# D1MiniRFM95.net
KiCad netlist of a schematic drawn in EAGLE
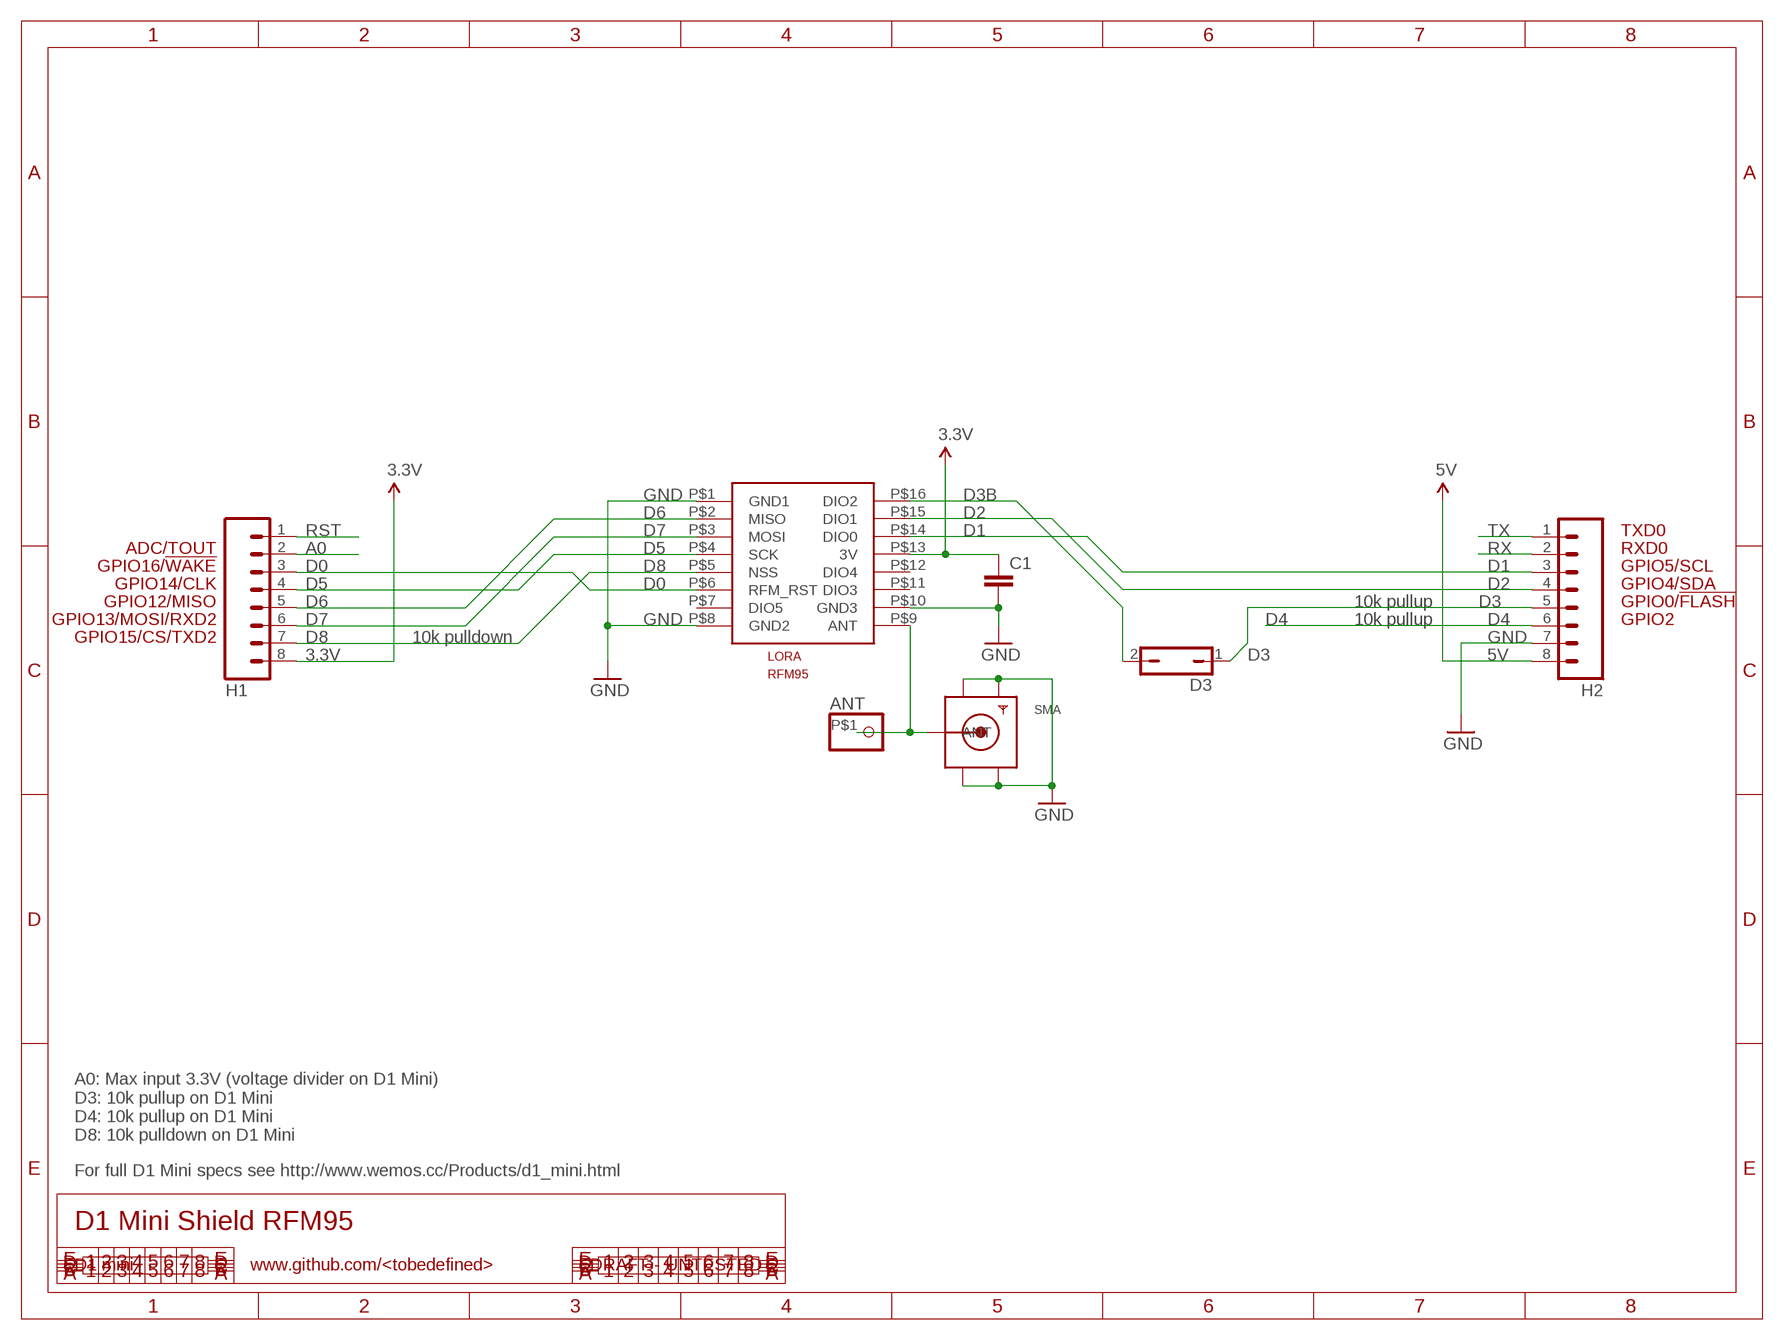
[diagram p0: schematic, sheet 1]

(export (version "E")
  (design (tool "Eeschema 10.0.6"))
  (components
    (comp (ref "ANT")
      (value "PINHD-1X1-BIGPOGO")
      (footprint "eagle-import:1X1-BIGPOGO")
      (libsource (lib "eagle-import") (part "PINHD-1X1-BIGPOGO"))
    )
    (comp (ref "C1")
      (value "C-EU025-024X044")
      (footprint "eagle-import:C025-024X044")
      (libsource (lib "eagle-import") (part "C-EU025-024X044"))
    )
    (comp (ref "D3")
      (value "JP1Q")
      (footprint "eagle-import:JP1")
      (libsource (lib "eagle-import") (part "JP1Q"))
    )
    (comp (ref "H1")
      (value "M08")
      (footprint "eagle-import:1X08")
      (libsource (lib "eagle-import") (part "M08"))
    )
    (comp (ref "H2")
      (value "M08")
      (footprint "eagle-import:1X08")
      (libsource (lib "eagle-import") (part "M08"))
    )
    (comp (ref "LORA")
      (value "RFM95")
      (footprint "eagle-import:RFM95")
      (libsource (lib "eagle-import") (part "RFM95"))
    )
    (comp (ref "SMA")
      (value "SMACONNECTOR_EDGE")
      (footprint "eagle-import:SMA_EDGELAUNCH")
      (libsource (lib "eagle-import") (part "SMACONNECTOR_EDGE"))
    )
  )
  (nets
    (net (code "1") (name "/A0") (class "Default")
      (node (ref "H1") (pin "2") (pinfunction "2_2") (pintype "passive"))
    )
    (net (code "2") (name "/D0") (class "Default")
      (node (ref "H1") (pin "3") (pinfunction "3_3") (pintype "passive"))
      (node (ref "LORA") (pin "P$6") (pinfunction "RFM_RST_P$6") (pintype "bidirectional"))
    )
    (net (code "3") (name "/D1") (class "Default")
      (node (ref "H2") (pin "3") (pinfunction "3_3") (pintype "passive"))
      (node (ref "LORA") (pin "P$14") (pinfunction "DIO0_P$14") (pintype "bidirectional"))
    )
    (net (code "4") (name "/D2") (class "Default")
      (node (ref "H2") (pin "4") (pinfunction "4_4") (pintype "passive"))
      (node (ref "LORA") (pin "P$15") (pinfunction "DIO1_P$15") (pintype "bidirectional"))
    )
    (net (code "5") (name "/D3") (class "Default")
      (node (ref "D3") (pin "1") (pinfunction "1_1") (pintype "passive"))
      (node (ref "H2") (pin "5") (pinfunction "5_5") (pintype "passive"))
    )
    (net (code "6") (name "/D3B") (class "Default")
      (node (ref "D3") (pin "2") (pinfunction "2_2") (pintype "passive"))
      (node (ref "LORA") (pin "P$16") (pinfunction "DIO2_P$16") (pintype "bidirectional"))
    )
    (net (code "7") (name "/D4") (class "Default")
      (node (ref "H2") (pin "6") (pinfunction "6_6") (pintype "passive"))
    )
    (net (code "8") (name "/D5") (class "Default")
      (node (ref "H1") (pin "4") (pinfunction "4_4") (pintype "passive"))
      (node (ref "LORA") (pin "P$4") (pinfunction "SCK_P$4") (pintype "bidirectional"))
    )
    (net (code "9") (name "/D6") (class "Default")
      (node (ref "H1") (pin "5") (pinfunction "5_5") (pintype "passive"))
      (node (ref "LORA") (pin "P$2") (pinfunction "MISO_P$2") (pintype "bidirectional"))
    )
    (net (code "10") (name "/D7") (class "Default")
      (node (ref "H1") (pin "6") (pinfunction "6_6") (pintype "passive"))
      (node (ref "LORA") (pin "P$3") (pinfunction "MOSI_P$3") (pintype "bidirectional"))
    )
    (net (code "11") (name "/D8") (class "Default")
      (node (ref "H1") (pin "7") (pinfunction "7_7") (pintype "passive"))
      (node (ref "LORA") (pin "P$5") (pinfunction "NSS_P$5") (pintype "bidirectional"))
    )
    (net (code "12") (name "/RST") (class "Default")
      (node (ref "H1") (pin "1") (pinfunction "1_1") (pintype "passive"))
    )
    (net (code "13") (name "/RX") (class "Default")
      (node (ref "H2") (pin "2") (pinfunction "2_2") (pintype "passive"))
    )
    (net (code "14") (name "/TX") (class "Default")
      (node (ref "H2") (pin "1") (pinfunction "1_1") (pintype "passive"))
    )
    (net (code "15") (name "3.3V") (class "Default")
      (node (ref "C1") (pin "1") (pinfunction "1_1") (pintype "passive"))
      (node (ref "H1") (pin "8") (pinfunction "8_8") (pintype "passive"))
      (node (ref "LORA") (pin "P$13") (pinfunction "3V_P$13") (pintype "bidirectional"))
    )
    (net (code "16") (name "5V") (class "Default")
      (node (ref "H2") (pin "8") (pinfunction "8_8") (pintype "passive"))
    )
    (net (code "17") (name "GND") (class "Default")
      (node (ref "C1") (pin "2") (pinfunction "2_2") (pintype "passive"))
      (node (ref "H2") (pin "7") (pinfunction "7_7") (pintype "passive"))
      (node (ref "LORA") (pin "P$1") (pinfunction "GND1_P$1") (pintype "bidirectional"))
      (node (ref "LORA") (pin "P$10") (pinfunction "GND3_P$10") (pintype "bidirectional"))
      (node (ref "LORA") (pin "P$8") (pinfunction "GND2_P$8") (pintype "bidirectional"))
      (node (ref "SMA") (pin "GND@1") (pinfunction "GND4_GND@1") (pintype "power_in"))
      (node (ref "SMA") (pin "GND@2") (pinfunction "GND3_GND@2") (pintype "power_in"))
      (node (ref "SMA") (pin "GND@3") (pinfunction "GND2_GND@3") (pintype "power_in"))
      (node (ref "SMA") (pin "GND@4") (pinfunction "GND1_GND@4") (pintype "power_in"))
    )
    (net (code "18") (name "Net-(ANT-1)") (class "Default")
      (node (ref "ANT") (pin "P$1") (pinfunction "1_P$1") (pintype "passive"))
      (node (ref "LORA") (pin "P$9") (pinfunction "ANT_P$9") (pintype "bidirectional"))
      (node (ref "SMA") (pin "P") (pinfunction "ANT_P") (pintype "bidirectional"))
    )
    (net (code "19") (name "unconnected-(LORA-DIO3-PadP$11)") (class "Default")
      (node (ref "LORA") (pin "P$11") (pinfunction "DIO3_P$11") (pintype "bidirectional"))
    )
    (net (code "20") (name "unconnected-(LORA-DIO4-PadP$12)") (class "Default")
      (node (ref "LORA") (pin "P$12") (pinfunction "DIO4_P$12") (pintype "bidirectional"))
    )
    (net (code "21") (name "unconnected-(LORA-DIO5-PadP$7)") (class "Default")
      (node (ref "LORA") (pin "P$7") (pinfunction "DIO5_P$7") (pintype "bidirectional"))
    )
  )
)
